# MAX30102_Heart-Rate_Sensor.net
KiCad netlist of a schematic drawn in Altium Designer
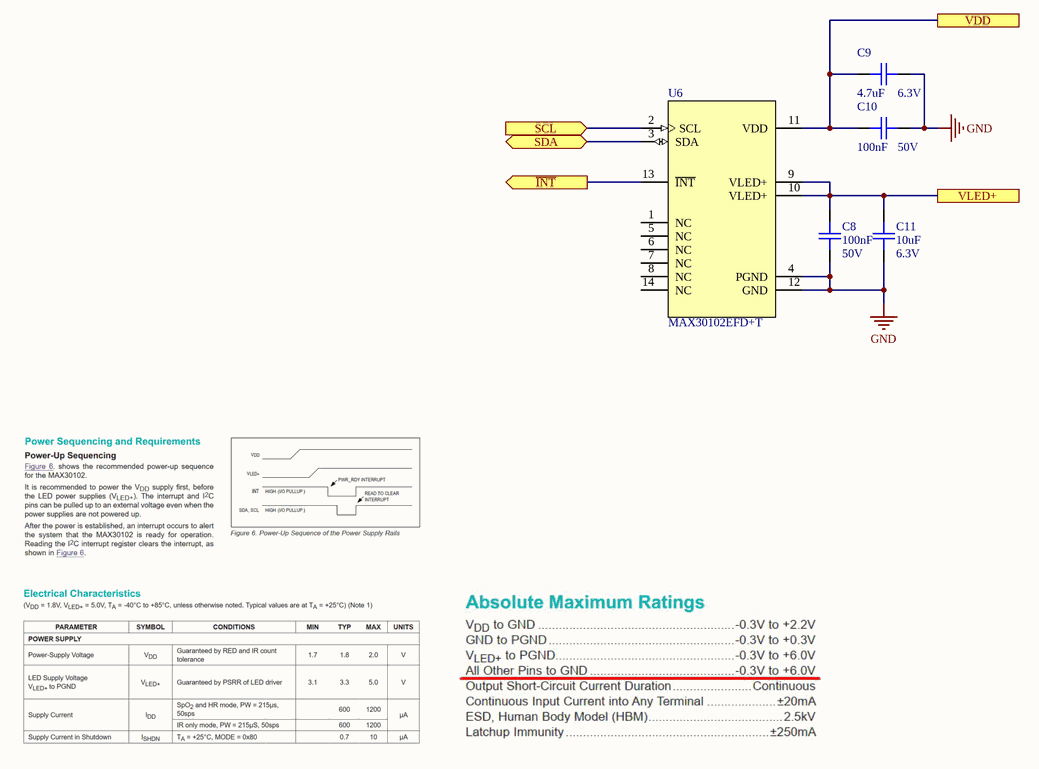
[diagram p0: MAX30102_Heart-Rate_Sensor.SchDoc]

(export (version "E")
  (design (tool "Eeschema 10.0.6"))
  (components
    (comp (ref "C8")
      (value "CAP CER 0.1UF 50V X7R 0402")
      (footprint "C0402")
      (description "0.1µF ±10% 50V Ceramic Capacitor X7R 0402 (1005 Metric)")
      (fields
        (field (name "MANUFACTURER") "TDK")
        (field (name "MANUFACTURER PART NUMBER") "CGA2B3X7R1H104K050BB")
        (field (name "CAPACITANCE") "100nF")
        (field (name "VOLTAGE") "50V")
      )
      (libsource (lib "capacitors_smd") (part "CAP CER 0.1UF 50V X7R 0402"))
    )
    (comp (ref "C9")
      (value "CAP CER 4.7UF 6.3V X5R 0402")
      (footprint "C0402")
      (description "4.7µF ±20% 6.3V Ceramic Capacitor X5R 0402 (1005 Metric)")
      (fields
        (field (name "MANUFACTURER") "Samsung")
        (field (name "MANUFACTURER PART NUMBER") "CL05A475MQ5NRNC")
        (field (name "CAPACITANCE") "4.7uF")
        (field (name "VOLTAGE RATING") "6.3V")
      )
      (libsource (lib "capacitors_smd") (part "CAP CER 4.7UF 6.3V X5R 0402"))
    )
    (comp (ref "C10")
      (value "CAP CER 0.1UF 50V X7R 0402")
      (footprint "C0402")
      (description "0.1µF ±10% 50V Ceramic Capacitor X7R 0402 (1005 Metric)")
      (fields
        (field (name "MANUFACTURER") "TDK")
        (field (name "MANUFACTURER PART NUMBER") "CGA2B3X7R1H104K050BB")
        (field (name "CAPACITANCE") "100nF")
        (field (name "VOLTAGE") "50V")
      )
      (libsource (lib "capacitors_smd") (part "CAP CER 0.1UF 50V X7R 0402"))
    )
    (comp (ref "C11")
      (value "CAP CER 10UF 6.3V X5R 0402")
      (footprint "C0402")
      (description "10µF ±20% 6.3V Ceramic Capacitor X5R 0402 (1005 Metric)")
      (fields
        (field (name "MANUFACTURER") "Samsung")
        (field (name "MANUFACTURER PART NUMBER") "CL05A106MQ5NUNC")
        (field (name "CAPACITANCE") "10uF")
        (field (name "VOLTAGE RATING") "6.3V")
      )
      (libsource (lib "capacitors_smd") (part "CAP CER 10UF 6.3V X5R 0402"))
    )
    (comp (ref "U6")
      (value "MAX30102EFD+T")
      (footprint "XDCR_MAX30101EFD+")
      (description "Oximeter/Heart Rate Sensor IÂ²C Output")
      (fields (field (name "MANUFACTURER") "Maxim"))
      (libsource (lib "BLDC_Motor_Driver") (part "IC MAX30102EFD+T INTEGRATED OPTICAL SENSOR"))
    )
  )
  (nets
    (net (code "1") (name "/INT") (class "Default")
      (node (ref "U6") (pin "13") (pinfunction "INT_13") (pintype "open_collector"))
    )
    (net (code "2") (name "/SCL") (class "Default")
      (node (ref "U6") (pin "2") (pinfunction "SCL_2") (pintype "input"))
    )
    (net (code "3") (name "/SDA") (class "Default")
      (node (ref "U6") (pin "3") (pinfunction "SDA_3") (pintype "bidirectional"))
    )
    (net (code "4") (name "/VDD") (class "Default")
      (node (ref "C10") (pin "1") (pinfunction "1_1") (pintype "passive"))
      (node (ref "C9") (pin "1") (pinfunction "1_1") (pintype "passive"))
      (node (ref "U6") (pin "11") (pinfunction "VDD_11") (pintype "power_in"))
    )
    (net (code "5") (name "/VLED+") (class "Default")
      (node (ref "C11") (pin "2") (pinfunction "2_2") (pintype "passive"))
      (node (ref "C8") (pin "2") (pinfunction "2_2") (pintype "passive"))
      (node (ref "U6") (pin "10") (pinfunction "VLED+_10") (pintype "power_in"))
      (node (ref "U6") (pin "9") (pinfunction "VLED+_9") (pintype "power_in"))
    )
    (net (code "6") (name "GND") (class "Default")
      (node (ref "C10") (pin "2") (pinfunction "2_2") (pintype "passive"))
      (node (ref "C11") (pin "1") (pinfunction "1_1") (pintype "passive"))
      (node (ref "C8") (pin "1") (pinfunction "1_1") (pintype "passive"))
      (node (ref "C9") (pin "2") (pinfunction "2_2") (pintype "passive"))
      (node (ref "U6") (pin "12") (pinfunction "GND_12") (pintype "power_in"))
      (node (ref "U6") (pin "4") (pinfunction "PGND_4") (pintype "power_in"))
    )
    (net (code "7") (name "unconnected-(U6-NC-Pad1)") (class "Default")
      (node (ref "U6") (pin "1") (pinfunction "NC_1") (pintype "passive"))
    )
    (net (code "8") (name "unconnected-(U6-NC-Pad5)") (class "Default")
      (node (ref "U6") (pin "5") (pinfunction "NC_5") (pintype "passive"))
    )
    (net (code "9") (name "unconnected-(U6-NC-Pad6)") (class "Default")
      (node (ref "U6") (pin "6") (pinfunction "NC_6") (pintype "passive"))
    )
    (net (code "10") (name "unconnected-(U6-NC-Pad7)") (class "Default")
      (node (ref "U6") (pin "7") (pinfunction "NC_7") (pintype "passive"))
    )
    (net (code "11") (name "unconnected-(U6-NC-Pad8)") (class "Default")
      (node (ref "U6") (pin "8") (pinfunction "NC_8") (pintype "passive"))
    )
    (net (code "12") (name "unconnected-(U6-NC-Pad14)") (class "Default")
      (node (ref "U6") (pin "14") (pinfunction "NC_14") (pintype "passive"))
    )
  )
)
